# moire_v1_2.net
KiCad netlist of a schematic drawn in EAGLE
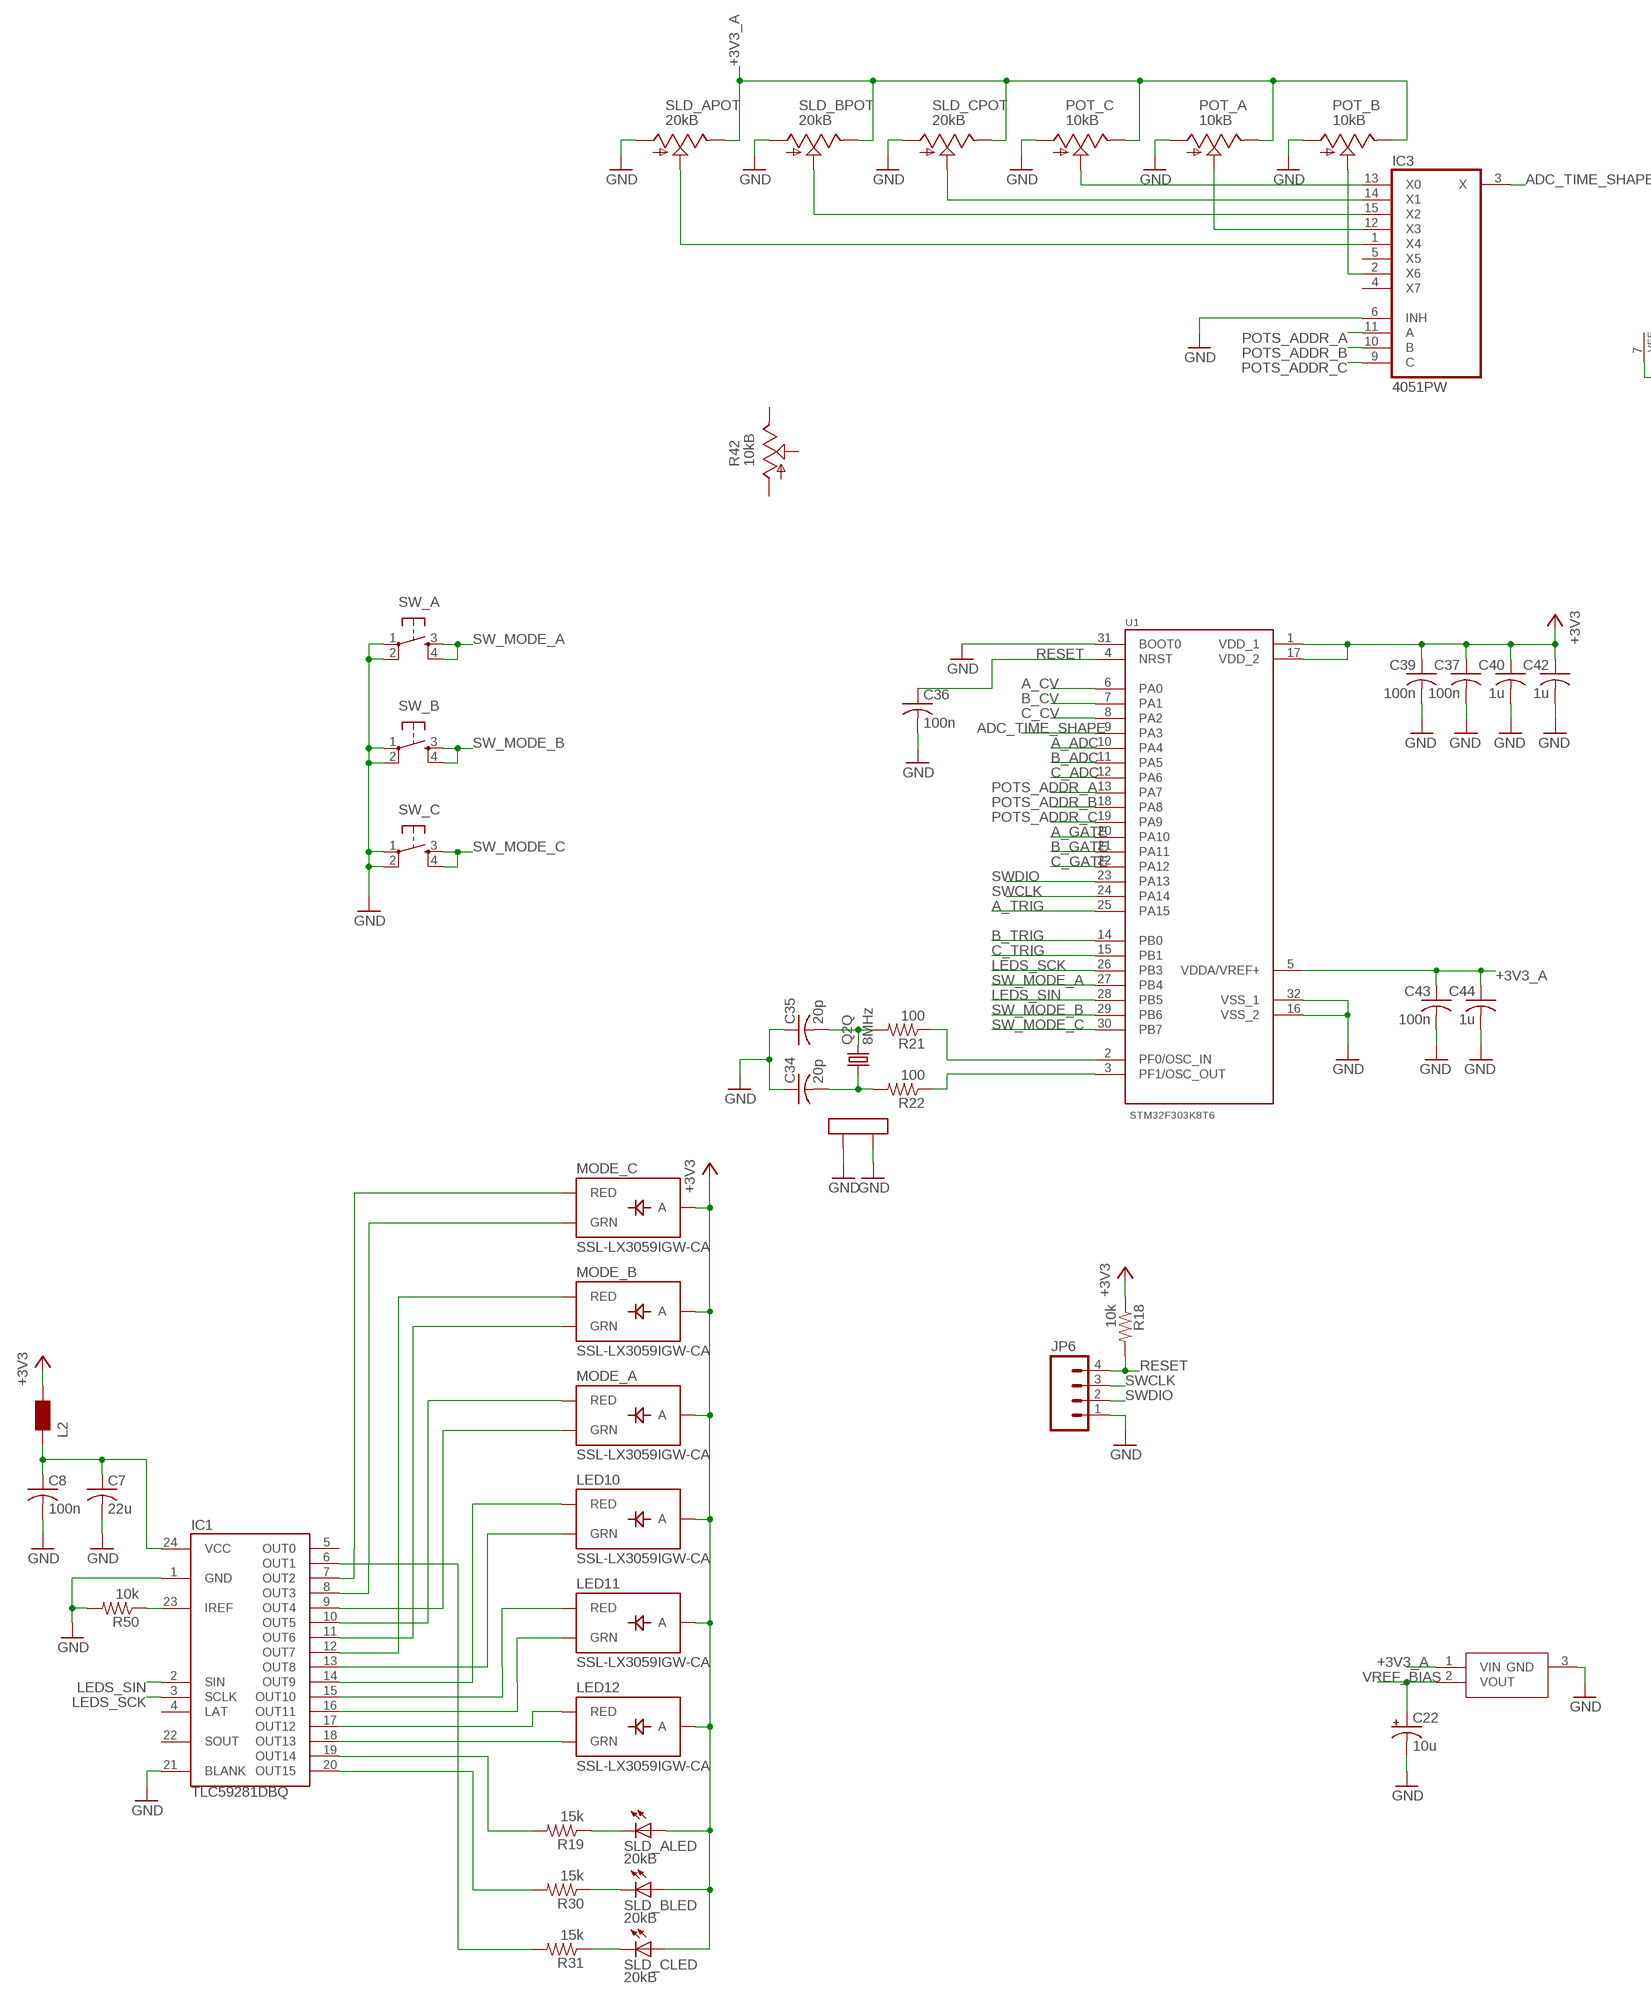
[diagram p0: schematic, sheet 1, part 1 of 2]
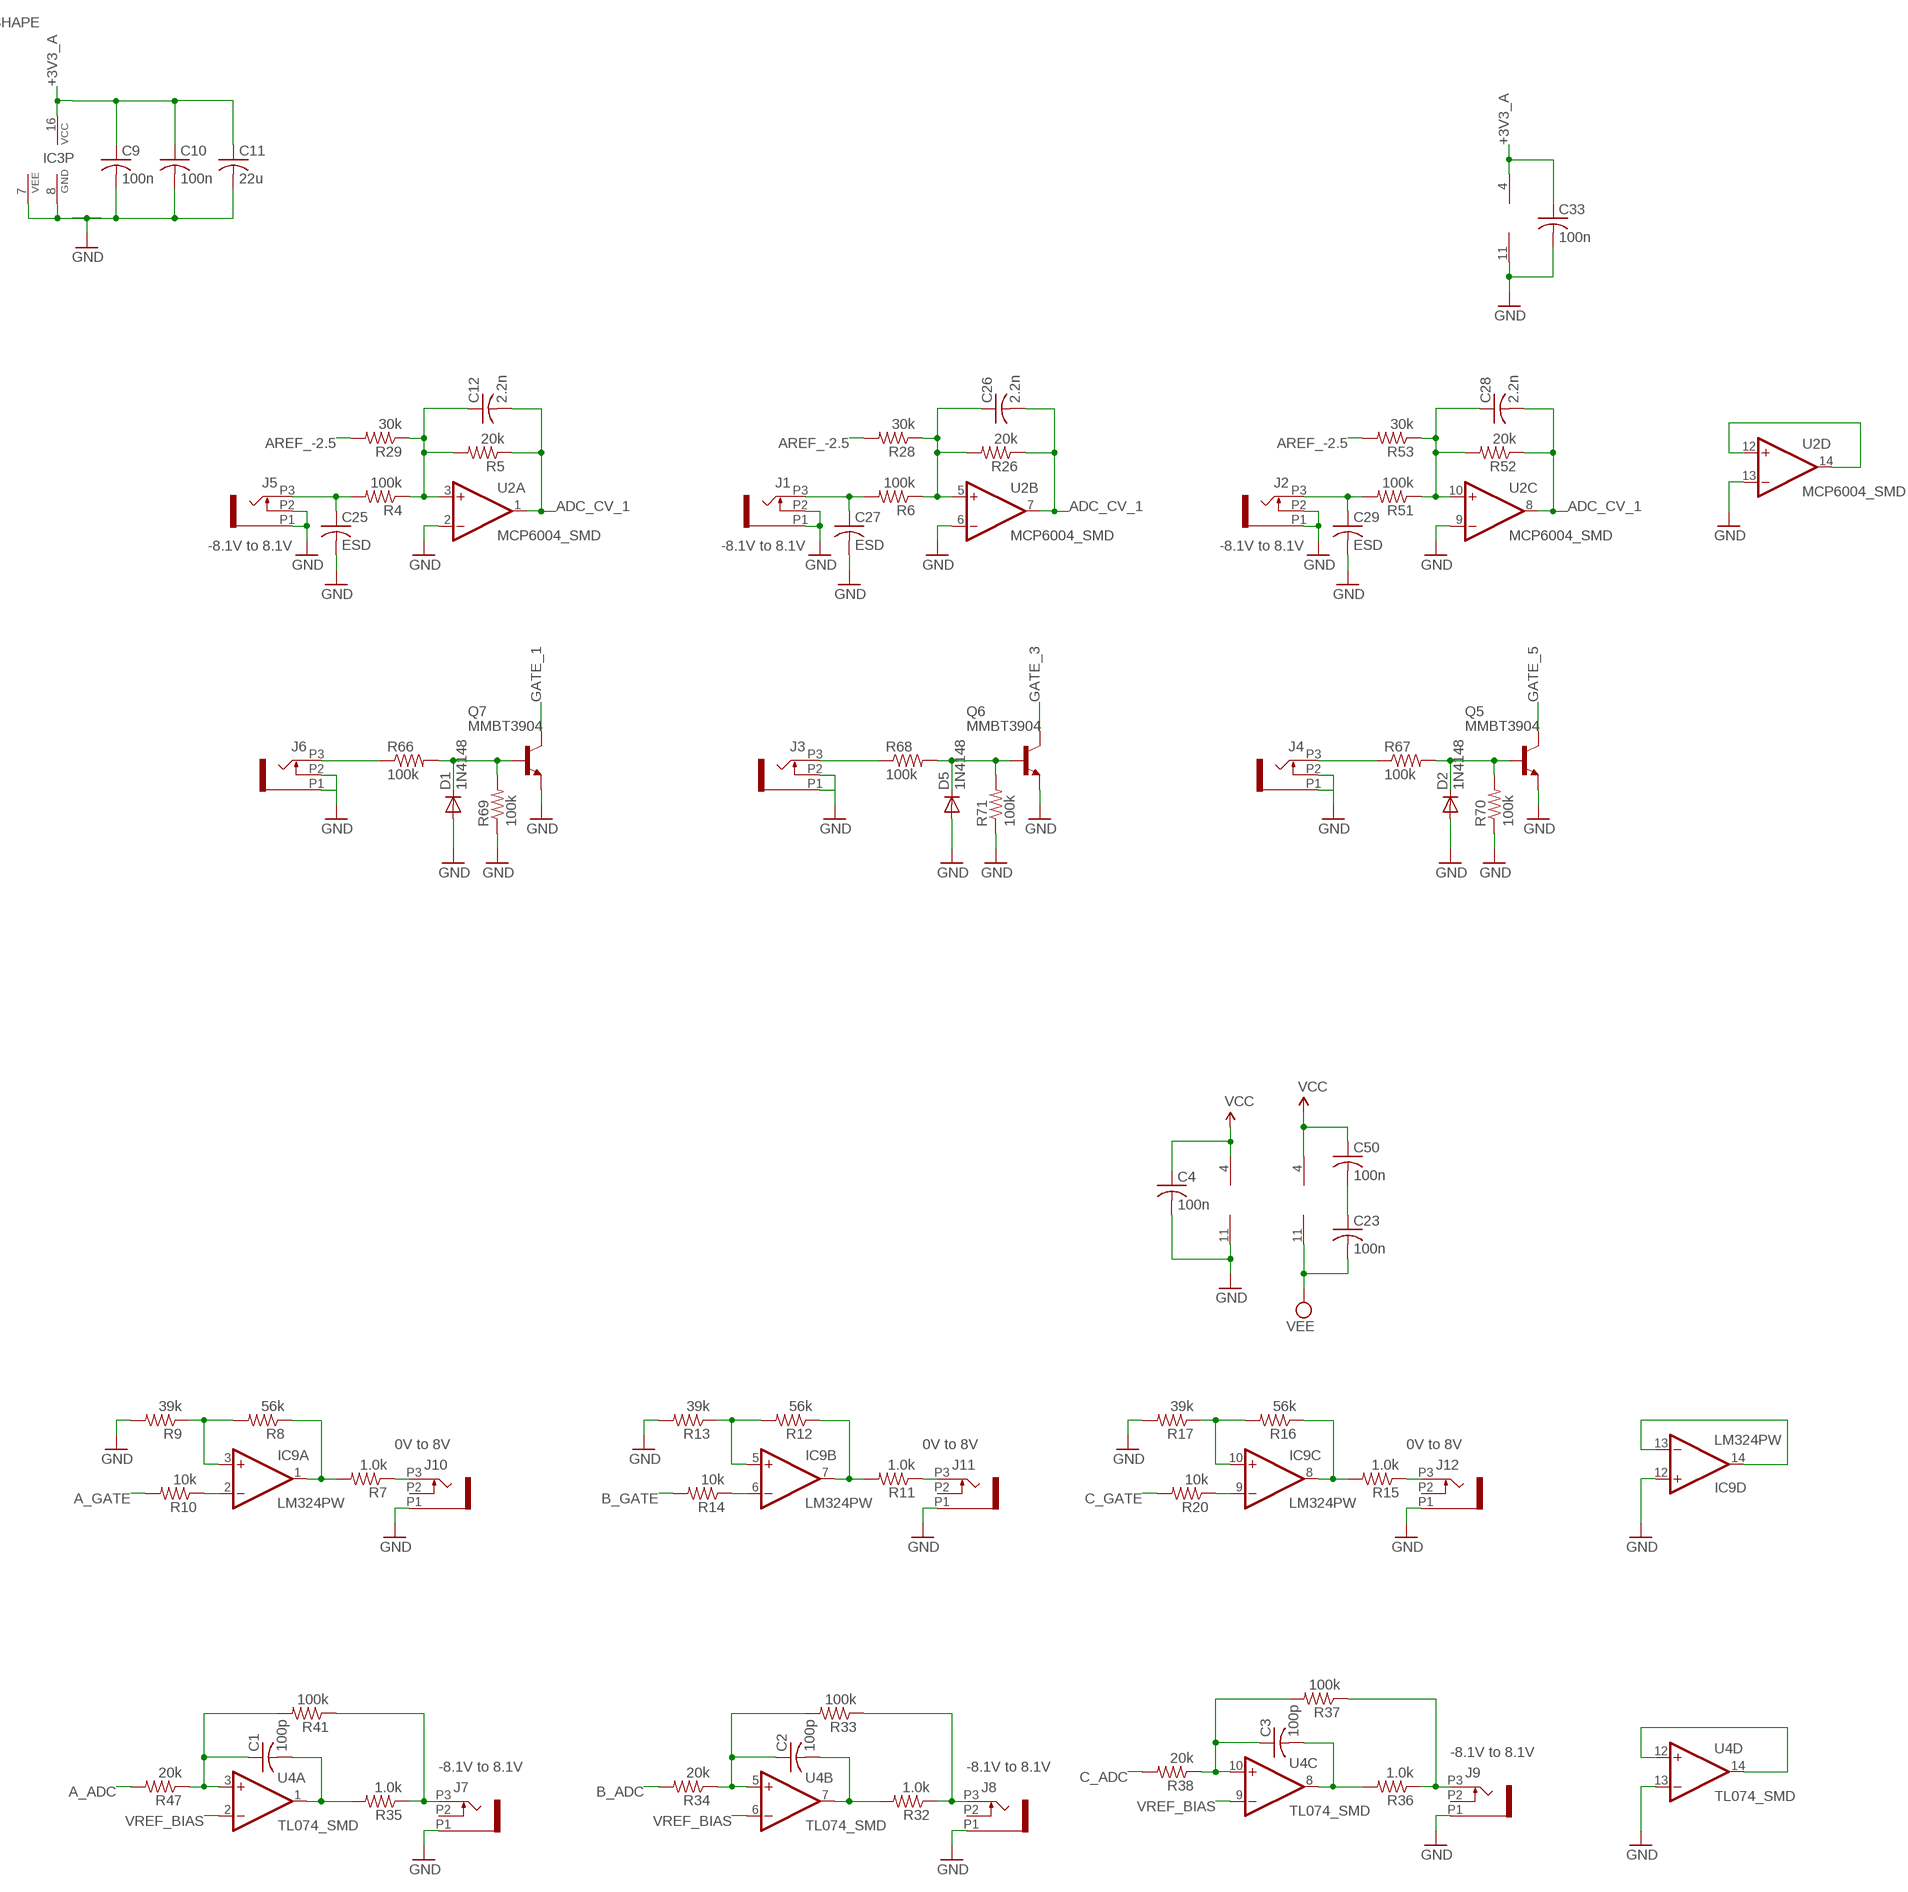
[diagram p1: schematic, sheet 1, part 2 of 2]
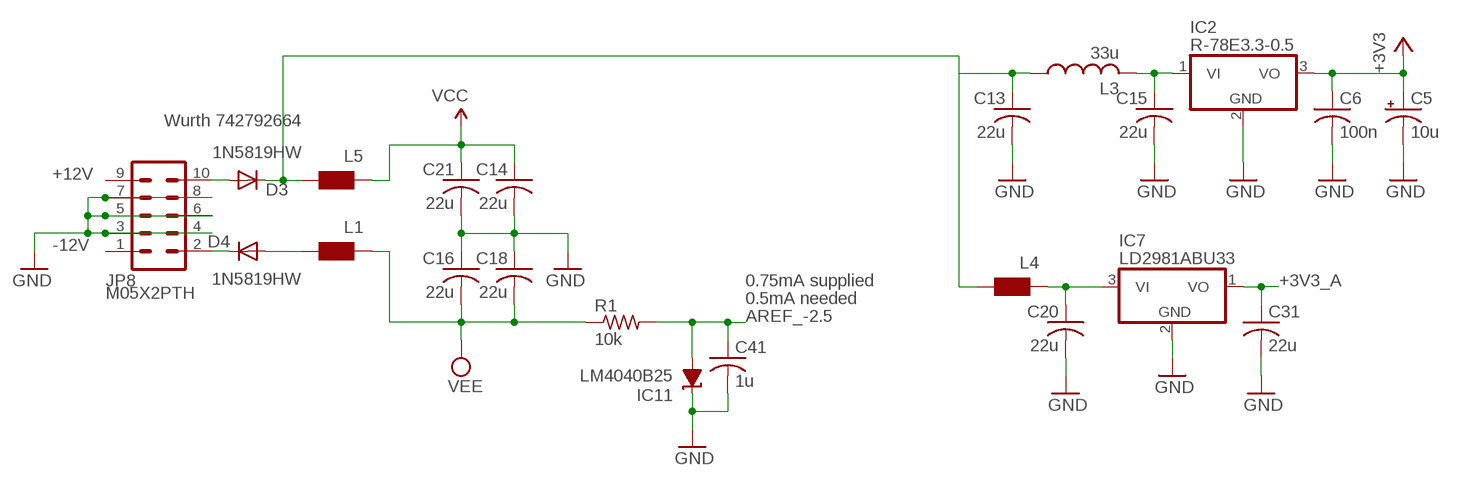
[diagram p2: schematic, sheet 2]

(export (version "E")
  (design (tool "Eeschema 10.0.6"))
  (components
    (comp (ref "C1")
      (value "100p")
      (footprint "eagle-import:C0603")
      (libsource (lib "eagle-import") (part "C-USC0603"))
    )
    (comp (ref "C2")
      (value "100p")
      (footprint "eagle-import:C0603")
      (libsource (lib "eagle-import") (part "C-USC0603"))
    )
    (comp (ref "C3")
      (value "100p")
      (footprint "eagle-import:C0603")
      (libsource (lib "eagle-import") (part "C-USC0603"))
    )
    (comp (ref "C4")
      (value "100n")
      (footprint "eagle-import:C0402")
      (libsource (lib "eagle-import") (part "C-USC0402"))
    )
    (comp (ref "C7")
      (value "22u")
      (footprint "eagle-import:C1206")
      (libsource (lib "eagle-import") (part "C-USC1206"))
    )
    (comp (ref "C8")
      (value "100n")
      (footprint "eagle-import:C0603")
      (libsource (lib "eagle-import") (part "C-USC0603"))
    )
    (comp (ref "C9")
      (value "100n")
      (footprint "eagle-import:C0603")
      (libsource (lib "eagle-import") (part "C-USC0603"))
    )
    (comp (ref "C10")
      (value "100n")
      (footprint "eagle-import:C0603")
      (libsource (lib "eagle-import") (part "C-USC0603"))
    )
    (comp (ref "C11")
      (value "22u")
      (footprint "eagle-import:C1206")
      (libsource (lib "eagle-import") (part "C-USC1206"))
    )
    (comp (ref "C12")
      (value "2.2n")
      (footprint "eagle-import:C0402")
      (libsource (lib "eagle-import") (part "C-USC0402"))
    )
    (comp (ref "C22")
      (value "10u")
      (footprint "eagle-import:PANASONIC_A")
      (libsource (lib "eagle-import") (part "CPOL-USA"))
    )
    (comp (ref "C23")
      (value "100n")
      (footprint "eagle-import:C0603")
      (libsource (lib "eagle-import") (part "C-USC0603"))
    )
    (comp (ref "C25")
      (value "ESD")
      (footprint "eagle-import:C0603")
      (libsource (lib "eagle-import") (part "C-USC0603"))
    )
    (comp (ref "C26")
      (value "2.2n")
      (footprint "eagle-import:C0402")
      (libsource (lib "eagle-import") (part "C-USC0402"))
    )
    (comp (ref "C27")
      (value "ESD")
      (footprint "eagle-import:C0603")
      (libsource (lib "eagle-import") (part "C-USC0603"))
    )
    (comp (ref "C28")
      (value "2.2n")
      (footprint "eagle-import:C0402")
      (libsource (lib "eagle-import") (part "C-USC0402"))
    )
    (comp (ref "C29")
      (value "ESD")
      (footprint "eagle-import:C0603")
      (libsource (lib "eagle-import") (part "C-USC0603"))
    )
    (comp (ref "C33")
      (value "100n")
      (footprint "eagle-import:C0603")
      (libsource (lib "eagle-import") (part "C-USC0603"))
    )
    (comp (ref "C34")
      (value "20p")
      (footprint "eagle-import:C0603")
      (libsource (lib "eagle-import") (part "C-USC0603"))
    )
    (comp (ref "C35")
      (value "20p")
      (footprint "eagle-import:C0603")
      (libsource (lib "eagle-import") (part "C-USC0603"))
    )
    (comp (ref "C36")
      (value "100n")
      (footprint "eagle-import:C0603")
      (libsource (lib "eagle-import") (part "C-USC0603"))
    )
    (comp (ref "C37")
      (value "100n")
      (footprint "eagle-import:C0603")
      (libsource (lib "eagle-import") (part "C-USC0603"))
    )
    (comp (ref "C39")
      (value "100n")
      (footprint "eagle-import:C0603")
      (libsource (lib "eagle-import") (part "C-USC0603"))
    )
    (comp (ref "C40")
      (value "1u")
      (footprint "eagle-import:C0603")
      (libsource (lib "eagle-import") (part "C-USC0603"))
    )
    (comp (ref "C42")
      (value "1u")
      (footprint "eagle-import:C0603")
      (libsource (lib "eagle-import") (part "C-USC0603"))
    )
    (comp (ref "C43")
      (value "100n")
      (footprint "eagle-import:C0603")
      (libsource (lib "eagle-import") (part "C-USC0603"))
    )
    (comp (ref "C44")
      (value "1u")
      (footprint "eagle-import:C0603")
      (libsource (lib "eagle-import") (part "C-USC0603"))
    )
    (comp (ref "C50")
      (value "100n")
      (footprint "eagle-import:C0603")
      (libsource (lib "eagle-import") (part "C-USC0603"))
    )
    (comp (ref "D1")
      (value "1N4148")
      (footprint "eagle-import:SOD523")
      (libsource (lib "eagle-import") (part "DIODE-SOD523"))
    )
    (comp (ref "D2")
      (value "1N4148")
      (footprint "eagle-import:SOD523")
      (libsource (lib "eagle-import") (part "DIODE-SOD523"))
    )
    (comp (ref "D5")
      (value "1N4148")
      (footprint "eagle-import:SOD523")
      (libsource (lib "eagle-import") (part "DIODE-SOD523"))
    )
    (comp (ref "IC1")
      (value "TLC59281DBQ")
      (footprint "eagle-import:TSSOP24_0635")
      (libsource (lib "eagle-import") (part "TLC59281DBQ"))
    )
    (comp (ref "IC3")
      (value "4051PW")
      (footprint "eagle-import:TSSOP16_065")
      (libsource (lib "eagle-import") (part "4051PW"))
    )
    (comp (ref "IC4")
      (value "LM324PW")
      (footprint "eagle-import:TSSOP14_065")
      (libsource (lib "eagle-import") (part "TL074PW"))
    )
    (comp (ref "IC9")
      (value "LM324PW")
      (footprint "eagle-import:TSSOP14_065")
      (libsource (lib "eagle-import") (part "TL074PW"))
    )
    (comp (ref "J1")
      (value "PJ301_THONKICONN6")
      (footprint "eagle-import:WQP_PJ_301M6")
      (libsource (lib "eagle-import") (part "PJ301_THONKICONN6"))
    )
    (comp (ref "J2")
      (value "PJ301_THONKICONN6")
      (footprint "eagle-import:WQP_PJ_301M6")
      (libsource (lib "eagle-import") (part "PJ301_THONKICONN6"))
    )
    (comp (ref "J3")
      (value "PJ301_THONKICONN6")
      (footprint "eagle-import:WQP_PJ_301M6")
      (libsource (lib "eagle-import") (part "PJ301_THONKICONN6"))
    )
    (comp (ref "J4")
      (value "PJ301_THONKICONN6")
      (footprint "eagle-import:WQP_PJ_301M6")
      (libsource (lib "eagle-import") (part "PJ301_THONKICONN6"))
    )
    (comp (ref "J5")
      (value "PJ301_THONKICONN6")
      (footprint "eagle-import:WQP_PJ_301M6")
      (libsource (lib "eagle-import") (part "PJ301_THONKICONN6"))
    )
    (comp (ref "J6")
      (value "PJ301_THONKICONN6")
      (footprint "eagle-import:WQP_PJ_301M6")
      (libsource (lib "eagle-import") (part "PJ301_THONKICONN6"))
    )
    (comp (ref "J7")
      (value "PJ301_THONKICONN6")
      (footprint "eagle-import:WQP_PJ_301M6")
      (libsource (lib "eagle-import") (part "PJ301_THONKICONN6"))
    )
    (comp (ref "J8")
      (value "PJ301_THONKICONN6")
      (footprint "eagle-import:WQP_PJ_301M6")
      (libsource (lib "eagle-import") (part "PJ301_THONKICONN6"))
    )
    (comp (ref "J9")
      (value "PJ301_THONKICONN6")
      (footprint "eagle-import:WQP_PJ_301M6")
      (libsource (lib "eagle-import") (part "PJ301_THONKICONN6"))
    )
    (comp (ref "J10")
      (value "PJ301_THONKICONN6")
      (footprint "eagle-import:WQP_PJ_301M6")
      (libsource (lib "eagle-import") (part "PJ301_THONKICONN6"))
    )
    (comp (ref "J11")
      (value "PJ301_THONKICONN6")
      (footprint "eagle-import:WQP_PJ_301M6")
      (libsource (lib "eagle-import") (part "PJ301_THONKICONN6"))
    )
    (comp (ref "J12")
      (value "PJ301_THONKICONN6")
      (footprint "eagle-import:WQP_PJ_301M6")
      (libsource (lib "eagle-import") (part "PJ301_THONKICONN6"))
    )
    (comp (ref "JP6")
      (value "M04PTH")
      (footprint "eagle-import:1X04")
      (libsource (lib "eagle-import") (part "M04PTH"))
    )
    (comp (ref "L2")
      (value "WE-CBF_0603")
      (footprint "eagle-import:0603")
      (libsource (lib "eagle-import") (part "WE-CBF_0603"))
    )
    (comp (ref "LED10")
      (value "SSL-LX3059IGW-CA")
      (footprint "eagle-import:LED-BICOLOR-THROUGHHOLE-LUMEX")
      (libsource (lib "eagle-import") (part "LED-BICOLOR-THROUGHHOLE-CA"))
    )
    (comp (ref "LED11")
      (value "SSL-LX3059IGW-CA")
      (footprint "eagle-import:LED-BICOLOR-THROUGHHOLE-LUMEX")
      (libsource (lib "eagle-import") (part "LED-BICOLOR-THROUGHHOLE-CA"))
    )
    (comp (ref "LED12")
      (value "SSL-LX3059IGW-CA")
      (footprint "eagle-import:LED-BICOLOR-THROUGHHOLE-LUMEX")
      (libsource (lib "eagle-import") (part "LED-BICOLOR-THROUGHHOLE-CA"))
    )
    (comp (ref "MODE_A")
      (value "SSL-LX3059IGW-CA")
      (footprint "eagle-import:LED-BICOLOR-THROUGHHOLE-LUMEX")
      (libsource (lib "eagle-import") (part "LED-BICOLOR-THROUGHHOLE-CA"))
    )
    (comp (ref "MODE_B")
      (value "SSL-LX3059IGW-CA")
      (footprint "eagle-import:LED-BICOLOR-THROUGHHOLE-LUMEX")
      (libsource (lib "eagle-import") (part "LED-BICOLOR-THROUGHHOLE-CA"))
    )
    (comp (ref "MODE_C")
      (value "SSL-LX3059IGW-CA")
      (footprint "eagle-import:LED-BICOLOR-THROUGHHOLE-LUMEX")
      (libsource (lib "eagle-import") (part "LED-BICOLOR-THROUGHHOLE-CA"))
    )
    (comp (ref "POT_A")
      (value "10kB")
      (footprint "eagle-import:ALPS_POT_VERTICAL")
      (libsource (lib "eagle-import") (part "POT_USVERTICAL"))
    )
    (comp (ref "POT_B")
      (value "10kB")
      (footprint "eagle-import:ALPS_POT_VERTICAL")
      (libsource (lib "eagle-import") (part "POT_USVERTICAL"))
    )
    (comp (ref "POT_C")
      (value "10kB")
      (footprint "eagle-import:ALPS_POT_VERTICAL")
      (libsource (lib "eagle-import") (part "POT_USVERTICAL"))
    )
    (comp (ref "Q2")
      (value "8MHz")
      (footprint "eagle-import:CTS406")
      (libsource (lib "eagle-import") (part "CRYSTAL"))
    )
    (comp (ref "Q5")
      (value "MMBT3904")
      (footprint "eagle-import:SOT23-BEC")
      (libsource (lib "eagle-import") (part "-NPN-SOT23-BECMMBT3904LT1"))
    )
    (comp (ref "Q6")
      (value "MMBT3904")
      (footprint "eagle-import:SOT23-BEC")
      (libsource (lib "eagle-import") (part "-NPN-SOT23-BECMMBT3904LT1"))
    )
    (comp (ref "Q7")
      (value "MMBT3904")
      (footprint "eagle-import:SOT23-BEC")
      (libsource (lib "eagle-import") (part "-NPN-SOT23-BECMMBT3904LT1"))
    )
    (comp (ref "R4")
      (value "100k")
      (footprint "eagle-import:R0603")
      (libsource (lib "eagle-import") (part "R-US_R0603"))
    )
    (comp (ref "R5")
      (value "20k")
      (footprint "eagle-import:R0603")
      (libsource (lib "eagle-import") (part "R-US_R0603"))
    )
    (comp (ref "R6")
      (value "100k")
      (footprint "eagle-import:R0603")
      (libsource (lib "eagle-import") (part "R-US_R0603"))
    )
    (comp (ref "R7")
      (value "1.0k")
      (footprint "eagle-import:R0603")
      (libsource (lib "eagle-import") (part "R-US_R0603"))
    )
    (comp (ref "R8")
      (value "56k")
      (footprint "eagle-import:R0603")
      (libsource (lib "eagle-import") (part "R-US_R0603"))
    )
    (comp (ref "R9")
      (value "39k")
      (footprint "eagle-import:R0603")
      (libsource (lib "eagle-import") (part "R-US_R0603"))
    )
    (comp (ref "R10")
      (value "10k")
      (footprint "eagle-import:R0603")
      (libsource (lib "eagle-import") (part "R-US_R0603"))
    )
    (comp (ref "R11")
      (value "1.0k")
      (footprint "eagle-import:R0603")
      (libsource (lib "eagle-import") (part "R-US_R0603"))
    )
    (comp (ref "R12")
      (value "56k")
      (footprint "eagle-import:R0603")
      (libsource (lib "eagle-import") (part "R-US_R0603"))
    )
    (comp (ref "R13")
      (value "39k")
      (footprint "eagle-import:R0603")
      (libsource (lib "eagle-import") (part "R-US_R0603"))
    )
    (comp (ref "R14")
      (value "10k")
      (footprint "eagle-import:R0603")
      (libsource (lib "eagle-import") (part "R-US_R0603"))
    )
    (comp (ref "R15")
      (value "1.0k")
      (footprint "eagle-import:R0603")
      (libsource (lib "eagle-import") (part "R-US_R0603"))
    )
    (comp (ref "R16")
      (value "56k")
      (footprint "eagle-import:R0603")
      (libsource (lib "eagle-import") (part "R-US_R0603"))
    )
    (comp (ref "R17")
      (value "39k")
      (footprint "eagle-import:R0603")
      (libsource (lib "eagle-import") (part "R-US_R0603"))
    )
    (comp (ref "R18")
      (value "10k")
      (footprint "eagle-import:R0603")
      (libsource (lib "eagle-import") (part "R-US_R0603"))
    )
    (comp (ref "R19")
      (value "15k")
      (footprint "eagle-import:R0603")
      (libsource (lib "eagle-import") (part "R-US_R0603"))
    )
    (comp (ref "R20")
      (value "10k")
      (footprint "eagle-import:R0603")
      (libsource (lib "eagle-import") (part "R-US_R0603"))
    )
    (comp (ref "R21")
      (value "100")
      (footprint "eagle-import:R0603")
      (libsource (lib "eagle-import") (part "R-US_R0603"))
    )
    (comp (ref "R22")
      (value "100")
      (footprint "eagle-import:R0603")
      (libsource (lib "eagle-import") (part "R-US_R0603"))
    )
    (comp (ref "R26")
      (value "20k")
      (footprint "eagle-import:R0603")
      (libsource (lib "eagle-import") (part "R-US_R0603"))
    )
    (comp (ref "R28")
      (value "30k")
      (footprint "eagle-import:R0603")
      (libsource (lib "eagle-import") (part "R-US_R0603"))
    )
    (comp (ref "R29")
      (value "30k")
      (footprint "eagle-import:R0603")
      (libsource (lib "eagle-import") (part "R-US_R0603"))
    )
    (comp (ref "R30")
      (value "15k")
      (footprint "eagle-import:R0603")
      (libsource (lib "eagle-import") (part "R-US_R0603"))
    )
    (comp (ref "R31")
      (value "15k")
      (footprint "eagle-import:R0603")
      (libsource (lib "eagle-import") (part "R-US_R0603"))
    )
    (comp (ref "R32")
      (value "1.0k")
      (footprint "eagle-import:R0603")
      (libsource (lib "eagle-import") (part "R-US_R0603"))
    )
    (comp (ref "R33")
      (value "100k")
      (footprint "eagle-import:R0603")
      (libsource (lib "eagle-import") (part "R-US_R0603"))
    )
    (comp (ref "R34")
      (value "20k")
      (footprint "eagle-import:R0603")
      (libsource (lib "eagle-import") (part "R-US_R0603"))
    )
    (comp (ref "R35")
      (value "1.0k")
      (footprint "eagle-import:R0603")
      (libsource (lib "eagle-import") (part "R-US_R0603"))
    )
    (comp (ref "R36")
      (value "1.0k")
      (footprint "eagle-import:R0603")
      (libsource (lib "eagle-import") (part "R-US_R0603"))
    )
    (comp (ref "R37")
      (value "100k")
      (footprint "eagle-import:R0603")
      (libsource (lib "eagle-import") (part "R-US_R0603"))
    )
    (comp (ref "R38")
      (value "20k")
      (footprint "eagle-import:R0603")
      (libsource (lib "eagle-import") (part "R-US_R0603"))
    )
    (comp (ref "R41")
      (value "100k")
      (footprint "eagle-import:R0603")
      (libsource (lib "eagle-import") (part "R-US_R0603"))
    )
    (comp (ref "R42")
      (value "10kB")
      (footprint "eagle-import:ALPS_POT_VERTICAL")
      (libsource (lib "eagle-import") (part "POT_USVERTICAL"))
    )
    (comp (ref "R47")
      (value "20k")
      (footprint "eagle-import:R0603")
      (libsource (lib "eagle-import") (part "R-US_R0603"))
    )
    (comp (ref "R50")
      (value "10k")
      (footprint "eagle-import:R0603")
      (libsource (lib "eagle-import") (part "R-US_R0603"))
    )
    (comp (ref "R51")
      (value "100k")
      (footprint "eagle-import:R0603")
      (libsource (lib "eagle-import") (part "R-US_R0603"))
    )
    (comp (ref "R52")
      (value "20k")
      (footprint "eagle-import:R0603")
      (libsource (lib "eagle-import") (part "R-US_R0603"))
    )
    (comp (ref "R53")
      (value "30k")
      (footprint "eagle-import:R0603")
      (libsource (lib "eagle-import") (part "R-US_R0603"))
    )
    (comp (ref "R66")
      (value "100k")
      (footprint "eagle-import:R0603")
      (libsource (lib "eagle-import") (part "R-US_R0603"))
    )
    (comp (ref "R67")
      (value "100k")
      (footprint "eagle-import:R0603")
      (libsource (lib "eagle-import") (part "R-US_R0603"))
    )
    (comp (ref "R68")
      (value "100k")
      (footprint "eagle-import:R0603")
      (libsource (lib "eagle-import") (part "R-US_R0603"))
    )
    (comp (ref "R69")
      (value "100k")
      (footprint "eagle-import:R0603")
      (libsource (lib "eagle-import") (part "R-US_R0603"))
    )
    (comp (ref "R70")
      (value "100k")
      (footprint "eagle-import:R0603")
      (libsource (lib "eagle-import") (part "R-US_R0603"))
    )
    (comp (ref "R71")
      (value "100k")
      (footprint "eagle-import:R0603")
      (libsource (lib "eagle-import") (part "R-US_R0603"))
    )
    (comp (ref "SLD_A")
      (value "20kB")
      (footprint "eagle-import:BOURNS_SLIDER")
      (libsource (lib "eagle-import") (part "BOURNS_SLIDER"))
    )
    (comp (ref "SLD_B")
      (value "20kB")
      (footprint "eagle-import:BOURNS_SLIDER")
      (libsource (lib "eagle-import") (part "BOURNS_SLIDER"))
    )
    (comp (ref "SLD_C")
      (value "20kB")
      (footprint "eagle-import:BOURNS_SLIDER")
      (libsource (lib "eagle-import") (part "BOURNS_SLIDER"))
    )
    (comp (ref "SW_A")
      (value "TAC_SWITCHPTH")
      (footprint "eagle-import:TACTILE-PTH")
      (libsource (lib "eagle-import") (part "TAC_SWITCHPTH"))
    )
    (comp (ref "SW_B")
      (value "TAC_SWITCHPTH")
      (footprint "eagle-import:TACTILE-PTH")
      (libsource (lib "eagle-import") (part "TAC_SWITCHPTH"))
    )
    (comp (ref "SW_C")
      (value "TAC_SWITCHPTH")
      (footprint "eagle-import:TACTILE-PTH")
      (libsource (lib "eagle-import") (part "TAC_SWITCHPTH"))
    )
    (comp (ref "U$1")
      (value "ISL21010")
      (footprint "eagle-import:SOT-23-3")
      (libsource (lib "eagle-import") (part "ISL21010"))
    )
    (comp (ref "U1")
      (value "STM32F303K8T6")
      (footprint "eagle-import:QFP80P900X900X160-32N")
      (fields (field (name "MF") "STMicroelectronics"))
      (libsource (lib "eagle-import") (part "STM32F303K8T6"))
    )
    (comp (ref "U2")
      (value "MCP6004_SMD")
      (footprint "eagle-import:SO14")
      (libsource (lib "eagle-import") (part "MCP6004_SMD"))
    )
    (comp (ref "U4")
      (value "TL074_SMD")
      (footprint "eagle-import:SO14")
      (libsource (lib "eagle-import") (part "TL074_SMD"))
    )
    (comp (ref "C5")
      (value "10u")
      (footprint "eagle-import:PANASONIC_A")
      (libsource (lib "eagle-import") (part "CPOL-USA"))
    )
    (comp (ref "C6")
      (value "100n")
      (footprint "eagle-import:C0402")
      (libsource (lib "eagle-import") (part "C-USC0402"))
    )
    (comp (ref "C13")
      (value "22u")
      (footprint "eagle-import:C1206")
      (libsource (lib "eagle-import") (part "C-USC1206"))
    )
    (comp (ref "C14")
      (value "22u")
      (footprint "eagle-import:C1206")
      (libsource (lib "eagle-import") (part "C-USC1206"))
    )
    (comp (ref "C15")
      (value "22u")
      (footprint "eagle-import:C1206")
      (libsource (lib "eagle-import") (part "C-USC1206"))
    )
    (comp (ref "C16")
      (value "22u")
      (footprint "eagle-import:C1206")
      (libsource (lib "eagle-import") (part "C-USC1206"))
    )
    (comp (ref "C18")
      (value "22u")
      (footprint "eagle-import:C1206")
      (libsource (lib "eagle-import") (part "C-USC1206"))
    )
    (comp (ref "C20")
      (value "22u")
      (footprint "eagle-import:C1206")
      (libsource (lib "eagle-import") (part "C-USC1206"))
    )
    (comp (ref "C21")
      (value "22u")
      (footprint "eagle-import:C1206")
      (libsource (lib "eagle-import") (part "C-USC1206"))
    )
    (comp (ref "C31")
      (value "22u")
      (footprint "eagle-import:C1206")
      (libsource (lib "eagle-import") (part "C-USC1206"))
    )
    (comp (ref "C41")
      (value "1u")
      (footprint "eagle-import:C0402")
      (libsource (lib "eagle-import") (part "C-USC0402"))
    )
    (comp (ref "D3")
      (value "1N5819HW")
      (footprint "eagle-import:SOD123")
      (libsource (lib "eagle-import") (part "DIODE-SOD123"))
    )
    (comp (ref "D4")
      (value "1N5819HW")
      (footprint "eagle-import:SOD123")
      (libsource (lib "eagle-import") (part "DIODE-SOD123"))
    )
    (comp (ref "IC2")
      (value "R-78E3.3-0.5")
      (footprint "eagle-import:WE78")
      (libsource (lib "eagle-import") (part "WE173950378"))
    )
    (comp (ref "IC7")
      (value "LD2981ABU33")
      (footprint "eagle-import:SOT89")
      (libsource (lib "eagle-import") (part "LD2981ABU"))
    )
    (comp (ref "IC11")
      (value "LM4040B25")
      (footprint "eagle-import:DBZ_R-PDSO-G3")
      (libsource (lib "eagle-import") (part "LM4041DBZB12"))
    )
    (comp (ref "JP8")
      (value "M05X2PTH")
      (footprint "eagle-import:2X5-PTH")
      (libsource (lib "eagle-import") (part "M05X2PTH"))
    )
    (comp (ref "L1")
      (value "WE-CBF_0603")
      (footprint "eagle-import:0603")
      (libsource (lib "eagle-import") (part "WE-CBF_0603"))
    )
    (comp (ref "L3")
      (value "33u")
      (footprint "eagle-import:L2012C")
      (libsource (lib "eagle-import") (part "L-USL2012C"))
    )
    (comp (ref "L4")
      (value "WE-CBF_0603")
      (footprint "eagle-import:0603")
      (libsource (lib "eagle-import") (part "WE-CBF_0603"))
    )
    (comp (ref "L5")
      (value "WE-CBF_0603")
      (footprint "eagle-import:0603")
      (libsource (lib "eagle-import") (part "WE-CBF_0603"))
    )
    (comp (ref "R1")
      (value "10k")
      (footprint "eagle-import:R0603")
      (libsource (lib "eagle-import") (part "R-US_R0603"))
    )
  )
  (nets
    (net (code "1") (name "+3V3") (class "Default")
      (node (ref "C37") (pin "1") (pinfunction "1_1") (pintype "passive"))
      (node (ref "C39") (pin "1") (pinfunction "1_1") (pintype "passive"))
      (node (ref "C40") (pin "1") (pinfunction "1_1") (pintype "passive"))
      (node (ref "C42") (pin "1") (pinfunction "1_1") (pintype "passive"))
      (node (ref "C5") (pin "+") (pinfunction "+_+") (pintype "passive"))
      (node (ref "C6") (pin "1") (pinfunction "1_1") (pintype "passive"))
      (node (ref "IC2") (pin "3") (pinfunction "VO_3") (pintype "passive"))
      (node (ref "L2") (pin "2") (pinfunction "2_2") (pintype "passive"))
      (node (ref "LED10") (pin "A") (pinfunction "A_A") (pintype "bidirectional"))
      (node (ref "LED11") (pin "A") (pinfunction "A_A") (pintype "bidirectional"))
      (node (ref "LED12") (pin "A") (pinfunction "A_A") (pintype "bidirectional"))
      (node (ref "MODE_A") (pin "A") (pinfunction "A_A") (pintype "bidirectional"))
      (node (ref "MODE_B") (pin "A") (pinfunction "A_A") (pintype "bidirectional"))
      (node (ref "MODE_C") (pin "A") (pinfunction "A_A") (pintype "bidirectional"))
      (node (ref "R18") (pin "1") (pinfunction "1_1") (pintype "passive"))
      (node (ref "SLD_A") (pin "B") (pinfunction "A_B") (pintype "passive"))
      (node (ref "SLD_B") (pin "B") (pinfunction "A_B") (pintype "passive"))
      (node (ref "SLD_C") (pin "B") (pinfunction "A_B") (pintype "passive"))
      (node (ref "U1") (pin "1") (pinfunction "VDD_1_1") (pintype "power_in"))
      (node (ref "U1") (pin "17") (pinfunction "VDD_2_17") (pintype "power_in"))
    )
    (net (code "2") (name "+3V3_A") (class "Default")
      (node (ref "C10") (pin "1") (pinfunction "1_1") (pintype "passive"))
      (node (ref "C11") (pin "1") (pinfunction "1_1") (pintype "passive"))
      (node (ref "C31") (pin "1") (pinfunction "1_1") (pintype "passive"))
      (node (ref "C33") (pin "1") (pinfunction "1_1") (pintype "passive"))
      (node (ref "C43") (pin "1") (pinfunction "1_1") (pintype "passive"))
      (node (ref "C44") (pin "1") (pinfunction "1_1") (pintype "passive"))
      (node (ref "C9") (pin "1") (pinfunction "1_1") (pintype "passive"))
      (node (ref "IC3") (pin "16") (pinfunction "VCC_16") (pintype "power_in"))
      (node (ref "IC7") (pin "1") (pinfunction "VO_1") (pintype "passive"))
      (node (ref "POT_A") (pin "P$1") (pinfunction "E_P$1") (pintype "passive"))
      (node (ref "POT_B") (pin "P$1") (pinfunction "E_P$1") (pintype "passive"))
      (node (ref "POT_C") (pin "P$1") (pinfunction "E_P$1") (pintype "passive"))
      (node (ref "SLD_A") (pin "3") (pinfunction "E_3") (pintype "passive"))
      (node (ref "SLD_B") (pin "3") (pinfunction "E_3") (pintype "passive"))
      (node (ref "SLD_C") (pin "3") (pinfunction "E_3") (pintype "passive"))
      (node (ref "U$1") (pin "1") (pinfunction "VIN_1") (pintype "input"))
      (node (ref "U1") (pin "5") (pinfunction "VDDA/VREF+_5") (pintype "power_in"))
      (node (ref "U2") (pin "4") (pinfunction "V+_4") (pintype "power_in"))
    )
    (net (code "3") (name "+12V") (class "Default")
      (node (ref "D3") (pin "A") (pinfunction "A_A") (pintype "passive"))
      (node (ref "JP8") (pin "10") (pinfunction "10_10") (pintype "passive"))
    )
    (net (code "4") (name "-12V") (class "Default")
      (node (ref "D4") (pin "C") (pinfunction "C_C") (pintype "passive"))
      (node (ref "JP8") (pin "2") (pinfunction "2_2") (pintype "passive"))
    )
    (net (code "5") (name "ADC_CV_1") (class "Default")
      (node (ref "C12") (pin "2") (pinfunction "2_2") (pintype "passive"))
      (node (ref "C26") (pin "2") (pinfunction "2_2") (pintype "passive"))
      (node (ref "C28") (pin "2") (pinfunction "2_2") (pintype "passive"))
      (node (ref "R26") (pin "1") (pinfunction "1_1") (pintype "passive"))
      (node (ref "R5") (pin "1") (pinfunction "1_1") (pintype "passive"))
      (node (ref "R52") (pin "1") (pinfunction "1_1") (pintype "passive"))
      (node (ref "U2") (pin "1") (pinfunction "OUT_1") (pintype "output"))
      (node (ref "U2") (pin "7") (pinfunction "OUT_7") (pintype "output"))
      (node (ref "U2") (pin "8") (pinfunction "OUT_8") (pintype "output"))
    )
    (net (code "6") (name "ADC_TIME_SHAPE") (class "Default")
      (node (ref "IC3") (pin "3") (pinfunction "X_3") (pintype "bidirectional"))
      (node (ref "U1") (pin "9") (pinfunction "PA3_9") (pintype "bidirectional"))
    )
    (net (code "7") (name "AREF_-2.5") (class "Default")
      (node (ref "C41") (pin "1") (pinfunction "1_1") (pintype "passive"))
      (node (ref "IC11") (pin "2") (pinfunction "A_2") (pintype "passive"))
      (node (ref "R1") (pin "2") (pinfunction "2_2") (pintype "passive"))
      (node (ref "R28") (pin "2") (pinfunction "2_2") (pintype "passive"))
      (node (ref "R29") (pin "2") (pinfunction "2_2") (pintype "passive"))
      (node (ref "R53") (pin "2") (pinfunction "2_2") (pintype "passive"))
    )
    (net (code "8") (name "A_ADC") (class "Default")
      (node (ref "R47") (pin "2") (pinfunction "2_2") (pintype "passive"))
      (node (ref "U1") (pin "10") (pinfunction "PA4_10") (pintype "bidirectional"))
    )
    (net (code "9") (name "A_CV") (class "Default")
      (node (ref "U1") (pin "6") (pinfunction "PA0_6") (pintype "bidirectional"))
    )
    (net (code "10") (name "A_GATE") (class "Default")
      (node (ref "R10") (pin "2") (pinfunction "2_2") (pintype "passive"))
      (node (ref "U1") (pin "20") (pinfunction "PA10_20") (pintype "bidirectional"))
    )
    (net (code "11") (name "A_TRIG") (class "Default")
      (node (ref "U1") (pin "25") (pinfunction "PA15_25") (pintype "bidirectional"))
    )
    (net (code "12") (name "B_ADC") (class "Default")
      (node (ref "R34") (pin "2") (pinfunction "2_2") (pintype "passive"))
      (node (ref "U1") (pin "11") (pinfunction "PA5_11") (pintype "bidirectional"))
    )
    (net (code "13") (name "B_CV") (class "Default")
      (node (ref "U1") (pin "7") (pinfunction "PA1_7") (pintype "bidirectional"))
    )
    (net (code "14") (name "B_GATE") (class "Default")
      (node (ref "R14") (pin "2") (pinfunction "2_2") (pintype "passive"))
      (node (ref "U1") (pin "21") (pinfunction "PA11_21") (pintype "bidirectional"))
    )
    (net (code "15") (name "B_TRIG") (class "Default")
      (node (ref "U1") (pin "14") (pinfunction "PB0_14") (pintype "bidirectional"))
    )
    (net (code "16") (name "C_ADC") (class "Default")
      (node (ref "R38") (pin "2") (pinfunction "2_2") (pintype "passive"))
      (node (ref "U1") (pin "12") (pinfunction "PA6_12") (pintype "bidirectional"))
    )
    (net (code "17") (name "C_CV") (class "Default")
      (node (ref "U1") (pin "8") (pinfunction "PA2_8") (pintype "bidirectional"))
    )
    (net (code "18") (name "C_GATE") (class "Default")
      (node (ref "R20") (pin "2") (pinfunction "2_2") (pintype "passive"))
      (node (ref "U1") (pin "22") (pinfunction "PA12_22") (pintype "bidirectional"))
    )
    (net (code "19") (name "C_TRIG") (class "Default")
      (node (ref "U1") (pin "15") (pinfunction "PB1_15") (pintype "bidirectional"))
    )
    (net (code "20") (name "GATE_1") (class "Default")
      (node (ref "Q7") (pin "C") (pinfunction "C_C") (pintype "passive"))
    )
    (net (code "21") (name "GATE_3") (class "Default")
      (node (ref "Q6") (pin "C") (pinfunction "C_C") (pintype "passive"))
    )
    (net (code "22") (name "GATE_5") (class "Default")
      (node (ref "Q5") (pin "C") (pinfunction "C_C") (pintype "passive"))
    )
    (net (code "23") (name "GND") (class "Default")
      (node (ref "C10") (pin "2") (pinfunction "2_2") (pintype "passive"))
      (node (ref "C11") (pin "2") (pinfunction "2_2") (pintype "passive"))
      (node (ref "C13") (pin "2") (pinfunction "2_2") (pintype "passive"))
      (node (ref "C14") (pin "2") (pinfunction "2_2") (pintype "passive"))
      (node (ref "C15") (pin "2") (pinfunction "2_2") (pintype "passive"))
      (node (ref "C16") (pin "1") (pinfunction "1_1") (pintype "passive"))
      (node (ref "C18") (pin "1") (pinfunction "1_1") (pintype "passive"))
      (node (ref "C20") (pin "2") (pinfunction "2_2") (pintype "passive"))
      (node (ref "C21") (pin "2") (pinfunction "2_2") (pintype "passive"))
      (node (ref "C22") (pin "-") (pinfunction "-_-") (pintype "passive"))
      (node (ref "C25") (pin "2") (pinfunction "2_2") (pintype "passive"))
      (node (ref "C27") (pin "2") (pinfunction "2_2") (pintype "passive"))
      (node (ref "C29") (pin "2") (pinfunction "2_2") (pintype "passive"))
      (node (ref "C31") (pin "2") (pinfunction "2_2") (pintype "passive"))
      (node (ref "C33") (pin "2") (pinfunction "2_2") (pintype "passive"))
      (node (ref "C34") (pin "1") (pinfunction "1_1") (pintype "passive"))
      (node (ref "C35") (pin "1") (pinfunction "1_1") (pintype "passive"))
      (node (ref "C36") (pin "2") (pinfunction "2_2") (pintype "passive"))
      (node (ref "C37") (pin "2") (pinfunction "2_2") (pintype "passive"))
      (node (ref "C39") (pin "2") (pinfunction "2_2") (pintype "passive"))
      (node (ref "C4") (pin "2") (pinfunction "2_2") (pintype "passive"))
      (node (ref "C40") (pin "2") (pinfunction "2_2") (pintype "passive"))
      (node (ref "C41") (pin "2") (pinfunction "2_2") (pintype "passive"))
      (node (ref "C42") (pin "2") (pinfunction "2_2") (pintype "passive"))
      (node (ref "C43") (pin "2") (pinfunction "2_2") (pintype "passive"))
      (node (ref "C44") (pin "2") (pinfunction "2_2") (pintype "passive"))
      (node (ref "C5") (pin "-") (pinfunction "-_-") (pintype "passive"))
      (node (ref "C6") (pin "2") (pinfunction "2_2") (pintype "passive"))
      (node (ref "C7") (pin "2") (pinfunction "2_2") (pintype "passive"))
      (node (ref "C8") (pin "2") (pinfunction "2_2") (pintype "passive"))
      (node (ref "C9") (pin "2") (pinfunction "2_2") (pintype "passive"))
      (node (ref "D1") (pin "A") (pinfunction "A_A") (pintype "passive"))
      (node (ref "D2") (pin "A") (pinfunction "A_A") (pintype "passive"))
      (node (ref "D5") (pin "A") (pinfunction "A_A") (pintype "passive"))
      (node (ref "IC1") (pin "1") (pinfunction "GND_1") (pintype "bidirectional"))
      (node (ref "IC1") (pin "21") (pinfunction "BLANK_21") (pintype "bidirectional"))
      (node (ref "IC11") (pin "1") (pinfunction "C_1") (pintype "passive"))
      (node (ref "IC2") (pin "2") (pinfunction "GND_2") (pintype "passive"))
      (node (ref "IC3") (pin "6") (pinfunction "INH_6") (pintype "input"))
      (node (ref "IC3") (pin "7") (pinfunction "VEE_7") (pintype "power_in"))
      (node (ref "IC3") (pin "8") (pinfunction "GND_8") (pintype "power_in"))
      (node (ref "IC4") (pin "11") (pinfunction "V-_11") (pintype "power_in"))
      (node (ref "IC7") (pin "2") (pinfunction "GND_2") (pintype "passive"))
      (node (ref "IC9") (pin "12") (pinfunction "+IN_12") (pintype "input"))
      (node (ref "J1") (pin "P1") (pinfunction "1_P1") (pintype "passive"))
      (node (ref "J1") (pin "P2") (pinfunction "2_P2") (pintype "passive"))
      (node (ref "J10") (pin "P1") (pinfunction "1_P1") (pintype "passive"))
      (node (ref "J11") (pin "P1") (pinfunction "1_P1") (pintype "passive"))
      (node (ref "J12") (pin "P1") (pinfunction "1_P1") (pintype "passive"))
      (node (ref "J2") (pin "P1") (pinfunction "1_P1") (pintype "passive"))
      (node (ref "J2") (pin "P2") (pinfunction "2_P2") (pintype "passive"))
      (node (ref "J3") (pin "P1") (pinfunction "1_P1") (pintype "passive"))
      (node (ref "J3") (pin "P2") (pinfunction "2_P2") (pintype "passive"))
      (node (ref "J4") (pin "P1") (pinfunction "1_P1") (pintype "passive"))
      (node (ref "J4") (pin "P2") (pinfunction "2_P2") (pintype "passive"))
      (node (ref "J5") (pin "P1") (pinfunction "1_P1") (pintype "passive"))
      (node (ref "J5") (pin "P2") (pinfunction "2_P2") (pintype "passive"))
      (node (ref "J6") (pin "P1") (pinfunction "1_P1") (pintype "passive"))
      (node (ref "J6") (pin "P2") (pinfunction "2_P2") (pintype "passive"))
      (node (ref "J7") (pin "P1") (pinfunction "1_P1") (pintype "passive"))
      (node (ref "J8") (pin "P1") (pinfunction "1_P1") (pintype "passive"))
      (node (ref "J9") (pin "P1") (pinfunction "1_P1") (pintype "passive"))
      (node (ref "JP6") (pin "1") (pinfunction "1_1") (pintype "passive"))
      (node (ref "JP8") (pin "3") (pinfunction "3_3") (pintype "passive"))
      (node (ref "JP8") (pin "4") (pinfunction "4_4") (pintype "passive"))
      (node (ref "JP8") (pin "5") (pinfunction "5_5") (pintype "passive"))
      (node (ref "JP8") (pin "6") (pinfunction "6_6") (pintype "passive"))
      (node (ref "JP8") (pin "7") (pinfunction "7_7") (pintype "passive"))
      (node (ref "JP8") (pin "8") (pinfunction "8_8") (pintype "passive"))
      (node (ref "POT_A") (pin "P$3") (pinfunction "A_P$3") (pintype "passive"))
      (node (ref "POT_B") (pin "P$3") (pinfunction "A_P$3") (pintype "passive"))
      (node (ref "POT_C") (pin "P$3") (pinfunction "A_P$3") (pintype "passive"))
      (node (ref "Q2") (pin "2") (pinfunction "LID1_2") (pintype "power_in"))
      (node (ref "Q2") (pin "4") (pinfunction "LID2_4") (pintype "power_in"))
      (node (ref "Q5") (pin "E") (pinfunction "E_E") (pintype "passive"))
      (node (ref "Q6") (pin "E") (pinfunction "E_E") (pintype "passive"))
      (node (ref "Q7") (pin "E") (pinfunction "E_E") (pintype "passive"))
      (node (ref "R13") (pin "2") (pinfunction "2_2") (pintype "passive"))
      (node (ref "R17") (pin "2") (pinfunction "2_2") (pintype "passive"))
      (node (ref "R50") (pin "2") (pinfunction "2_2") (pintype "passive"))
      (node (ref "R69") (pin "1") (pinfunction "1_1") (pintype "passive"))
      (node (ref "R70") (pin "1") (pinfunction "1_1") (pintype "passive"))
      (node (ref "R71") (pin "1") (pinfunction "1_1") (pintype "passive"))
      (node (ref "R9") (pin "2") (pinfunction "2_2") (pintype "passive"))
      (node (ref "SLD_A") (pin "1") (pinfunction "A_1") (pintype "passive"))
      (node (ref "SLD_B") (pin "1") (pinfunction "A_1") (pintype "passive"))
      (node (ref "SLD_C") (pin "1") (pinfunction "A_1") (pintype "passive"))
      (node (ref "SW_A") (pin "1") (pinfunction "1_1") (pintype "passive"))
      (node (ref "SW_A") (pin "2") (pinfunction "2_2") (pintype "passive"))
      (node (ref "SW_B") (pin "1") (pinfunction "1_1") (pintype "passive"))
      (node (ref "SW_B") (pin "2") (pinfunction "2_2") (pintype "passive"))
      (node (ref "SW_C") (pin "1") (pinfunction "1_1") (pintype "passive"))
      (node (ref "SW_C") (pin "2") (pinfunction "2_2") (pintype "passive"))
      (node (ref "U$1") (pin "3") (pinfunction "GND_3") (pintype "power_in"))
      (node (ref "U1") (pin "16") (pinfunction "VSS_2_16") (pintype "power_in"))
      (node (ref "U1") (pin "31") (pinfunction "BOOT0_31") (pintype "input"))
      (node (ref "U1") (pin "32") (pinfunction "VSS_1_32") (pintype "power_in"))
      (node (ref "U2") (pin "11") (pinfunction "V-_11") (pintype "power_in"))
      (node (ref "U2") (pin "13") (pinfunction "-IN_13") (pintype "input"))
      (node (ref "U2") (pin "2") (pinfunction "-IN_2") (pintype "input"))
      (node (ref "U2") (pin "6") (pinfunction "-IN_6") (pintype "input"))
      (node (ref "U2") (pin "9") (pinfunction "-IN_9") (pintype "input"))
      (node (ref "U4") (pin "13") (pinfunction "-IN_13") (pintype "input"))
    )
    (net (code "24") (name "LEDS_SCK") (class "Default")
      (node (ref "IC1") (pin "3") (pinfunction "SCLK_3") (pintype "bidirectional"))
      (node (ref "U1") (pin "26") (pinfunction "PB3_26") (pintype "bidirectional"))
    )
    (net (code "25") (name "LEDS_SIN") (class "Default")
      (node (ref "IC1") (pin "2") (pinfunction "SIN_2") (pintype "bidirectional"))
      (node (ref "U1") (pin "28") (pinfunction "PB5_28") (pintype "bidirectional"))
    )
    (net (code "26") (name "Net-(C13-Pad1)") (class "Default")
      (node (ref "C13") (pin "1") (pinfunction "1_1") (pintype "passive"))
      (node (ref "L3") (pin "1") (pinfunction "1_1") (pintype "passive"))
    )
    (net (code "27") (name "Net-(C23-Pad1)") (class "Default")
      (node (ref "C23") (pin "1") (pinfunction "1_1") (pintype "passive"))
      (node (ref "C50") (pin "2") (pinfunction "2_2") (pintype "passive"))
    )
    (net (code "28") (name "Net-(C34-Pad2)") (class "Default")
      (node (ref "C34") (pin "2") (pinfunction "2_2") (pintype "passive"))
      (node (ref "Q2") (pin "1") (pinfunction "1_1") (pintype "passive"))
      (node (ref "R22") (pin "2") (pinfunction "2_2") (pintype "passive"))
    )
    (net (code "29") (name "Net-(D1-PadC)") (class "Default")
      (node (ref "D1") (pin "C") (pinfunction "C_C") (pintype "passive"))
      (node (ref "Q7") (pin "B") (pinfunction "B_B") (pintype "passive"))
      (node (ref "R66") (pin "2") (pinfunction "2_2") (pintype "passive"))
      (node (ref "R69") (pin "2") (pinfunction "2_2") (pintype "passive"))
    )
    (net (code "30") (name "Net-(D2-PadC)") (class "Default")
      (node (ref "D2") (pin "C") (pinfunction "C_C") (pintype "passive"))
      (node (ref "Q5") (pin "B") (pinfunction "B_B") (pintype "passive"))
      (node (ref "R67") (pin "2") (pinfunction "2_2") (pintype "passive"))
      (node (ref "R70") (pin "2") (pinfunction "2_2") (pintype "passive"))
    )
    (net (code "31") (name "Net-(D3-PadC)") (class "Default")
      (node (ref "D3") (pin "C") (pinfunction "C_C") (pintype "passive"))
      (node (ref "L4") (pin "2") (pinfunction "2_2") (pintype "passive"))
      (node (ref "L5") (pin "2") (pinfunction "2_2") (pintype "passive"))
    )
    (net (code "32") (name "Net-(D4-PadA)") (class "Default")
      (node (ref "D4") (pin "A") (pinfunction "A_A") (pintype "passive"))
      (node (ref "L1") (pin "2") (pinfunction "2_2") (pintype "passive"))
    )
    (net (code "33") (name "Net-(D5-PadC)") (class "Default")
      (node (ref "D5") (pin "C") (pinfunction "C_C") (pintype "passive"))
      (node (ref "Q6") (pin "B") (pinfunction "B_B") (pintype "passive"))
      (node (ref "R68") (pin "2") (pinfunction "2_2") (pintype "passive"))
      (node (ref "R71") (pin "2") (pinfunction "2_2") (pintype "passive"))
    )
    (net (code "34") (name "Net-(IC1-IREF)") (class "Default")
      (node (ref "IC1") (pin "23") (pinfunction "IREF_23") (pintype "bidirectional"))
      (node (ref "R50") (pin "1") (pinfunction "1_1") (pintype "passive"))
    )
    (net (code "35") (name "Net-(IC1-OUT1)") (class "Default")
      (node (ref "IC1") (pin "6") (pinfunction "OUT1_6") (pintype "bidirectional"))
      (node (ref "R31") (pin "2") (pinfunction "2_2") (pintype "passive"))
    )
    (net (code "36") (name "Net-(IC1-OUT2)") (class "Default")
      (node (ref "IC1") (pin "7") (pinfunction "OUT2_7") (pintype "bidirectional"))
      (node (ref "MODE_C") (pin "RED_C") (pinfunction "RED_RED_C") (pintype "bidirectional"))
    )
    (net (code "37") (name "Net-(IC1-OUT3)") (class "Default")
      (node (ref "IC1") (pin "8") (pinfunction "OUT3_8") (pintype "bidirectional"))
      (node (ref "MODE_C") (pin "GREEN_C") (pinfunction "GRN_GREEN_C") (pintype "bidirectional"))
    )
    (net (code "38") (name "Net-(IC1-OUT4)") (class "Default")
      (node (ref "IC1") (pin "9") (pinfunction "OUT4_9") (pintype "bidirectional"))
      (node (ref "MODE_A") (pin "GREEN_C") (pinfunction "GRN_GREEN_C") (pintype "bidirectional"))
    )
    (net (code "39") (name "Net-(IC1-OUT5)") (class "Default")
      (node (ref "IC1") (pin "10") (pinfunction "OUT5_10") (pintype "bidirectional"))
      (node (ref "MODE_A") (pin "RED_C") (pinfunction "RED_RED_C") (pintype "bidirectional"))
    )
    (net (code "40") (name "Net-(IC1-OUT6)") (class "Default")
      (node (ref "IC1") (pin "11") (pinfunction "OUT6_11") (pintype "bidirectional"))
      (node (ref "MODE_B") (pin "GREEN_C") (pinfunction "GRN_GREEN_C") (pintype "bidirectional"))
    )
    (net (code "41") (name "Net-(IC1-OUT7)") (class "Default")
      (node (ref "IC1") (pin "12") (pinfunction "OUT7_12") (pintype "bidirectional"))
      (node (ref "MODE_B") (pin "RED_C") (pinfunction "RED_RED_C") (pintype "bidirectional"))
    )
    (net (code "42") (name "Net-(IC1-OUT8)") (class "Default")
      (node (ref "IC1") (pin "13") (pinfunction "OUT8_13") (pintype "bidirectional"))
      (node (ref "LED10") (pin "GREEN_C") (pinfunction "GRN_GREEN_C") (pintype "bidirectional"))
    )
    (net (code "43") (name "Net-(IC1-OUT9)") (class "Default")
      (node (ref "IC1") (pin "14") (pinfunction "OUT9_14") (pintype "bidirectional"))
      (node (ref "LED10") (pin "RED_C") (pinfunction "RED_RED_C") (pintype "bidirectional"))
    )
    (net (code "44") (name "Net-(IC1-OUT10)") (class "Default")
      (node (ref "IC1") (pin "15") (pinfunction "OUT10_15") (pintype "bidirectional"))
      (node (ref "LED11") (pin "RED_C") (pinfunction "RED_RED_C") (pintype "bidirectional"))
    )
    (net (code "45") (name "Net-(IC1-OUT11)") (class "Default")
      (node (ref "IC1") (pin "16") (pinfunction "OUT11_16") (pintype "bidirectional"))
      (node (ref "LED11") (pin "GREEN_C") (pinfunction "GRN_GREEN_C") (pintype "bidirectional"))
    )
    (net (code "46") (name "Net-(IC1-OUT12)") (class "Default")
      (node (ref "IC1") (pin "17") (pinfunction "OUT12_17") (pintype "bidirectional"))
      (node (ref "LED12") (pin "RED_C") (pinfunction "RED_RED_C") (pintype "bidirectional"))
    )
    (net (code "47") (name "Net-(IC1-OUT13)") (class "Default")
      (node (ref "IC1") (pin "18") (pinfunction "OUT13_18") (pintype "bidirectional"))
      (node (ref "LED12") (pin "GREEN_C") (pinfunction "GRN_GREEN_C") (pintype "bidirectional"))
    )
    (net (code "48") (name "Net-(IC1-OUT14)") (class "Default")
      (node (ref "IC1") (pin "19") (pinfunction "OUT14_19") (pintype "bidirectional"))
      (node (ref "R19") (pin "2") (pinfunction "2_2") (pintype "passive"))
    )
    (net (code "49") (name "Net-(IC1-OUT15)") (class "Default")
      (node (ref "IC1") (pin "20") (pinfunction "OUT15_20") (pintype "bidirectional"))
      (node (ref "R30") (pin "2") (pinfunction "2_2") (pintype "passive"))
    )
    (net (code "50") (name "Net-(IC1-VCC)") (class "Default")
      (node (ref "C7") (pin "1") (pinfunction "1_1") (pintype "passive"))
      (node (ref "C8") (pin "1") (pinfunction "1_1") (pintype "passive"))
      (node (ref "IC1") (pin "24") (pinfunction "VCC_24") (pintype "bidirectional"))
      (node (ref "L2") (pin "1") (pinfunction "1_1") (pintype "passive"))
    )
    (net (code "51") (name "Net-(IC2-VI)") (class "Default")
      (node (ref "C15") (pin "1") (pinfunction "1_1") (pintype "passive"))
      (node (ref "IC2") (pin "1") (pinfunction "VI_1") (pintype "input"))
      (node (ref "L3") (pin "2") (pinfunction "2_2") (pintype "passive"))
    )
    (net (code "52") (name "Net-(IC3A-X0)") (class "Default")
      (node (ref "IC3") (pin "13") (pinfunction "X0_13") (pintype "bidirectional"))
      (node (ref "POT_C") (pin "P$2") (pinfunction "S_P$2") (pintype "passive"))
    )
    (net (code "53") (name "Net-(IC3A-X1)") (class "Default")
      (node (ref "IC3") (pin "14") (pinfunction "X1_14") (pintype "bidirectional"))
      (node (ref "SLD_C") (pin "2") (pinfunction "S_2") (pintype "passive"))
    )
    (net (code "54") (name "Net-(IC3A-X2)") (class "Default")
      (node (ref "IC3") (pin "15") (pinfunction "X2_15") (pintype "bidirectional"))
      (node (ref "SLD_B") (pin "2") (pinfunction "S_2") (pintype "passive"))
    )
    (net (code "55") (name "Net-(IC3A-X3)") (class "Default")
      (node (ref "IC3") (pin "12") (pinfunction "X3_12") (pintype "bidirectional"))
      (node (ref "POT_A") (pin "P$2") (pinfunction "S_P$2") (pintype "passive"))
    )
    (net (code "56") (name "Net-(IC3A-X4)") (class "Default")
      (node (ref "IC3") (pin "1") (pinfunction "X4_1") (pintype "bidirectional"))
      (node (ref "SLD_A") (pin "2") (pinfunction "S_2") (pintype "passive"))
    )
    (net (code "57") (name "Net-(IC3A-X6)") (class "Default")
      (node (ref "IC3") (pin "2") (pinfunction "X6_2") (pintype "bidirectional"))
      (node (ref "POT_B") (pin "P$2") (pinfunction "S_P$2") (pintype "passive"))
    )
    (net (code "58") (name "Net-(IC7-VI)") (class "Default")
      (node (ref "C20") (pin "1") (pinfunction "1_1") (pintype "passive"))
      (node (ref "IC7") (pin "3") (pinfunction "VI_3") (pintype "input"))
      (node (ref "L4") (pin "1") (pinfunction "1_1") (pintype "passive"))
    )
    (net (code "59") (name "Net-(IC9A-+IN)") (class "Default")
      (node (ref "IC9") (pin "3") (pinfunction "+IN_3") (pintype "input"))
      (node (ref "R8") (pin "2") (pinfunction "2_2") (pintype "passive"))
      (node (ref "R9") (pin "1") (pinfunction "1_1") (pintype "passive"))
    )
    (net (code "60") (name "Net-(IC9A--IN)") (class "Default")
      (node (ref "IC9") (pin "2") (pinfunction "-IN_2") (pintype "input"))
      (node (ref "R10") (pin "1") (pinfunction "1_1") (pintype "passive"))
    )
    (net (code "61") (name "Net-(IC9A-OUT)") (class "Default")
      (node (ref "IC9") (pin "1") (pinfunction "OUT_1") (pintype "output"))
      (node (ref "R7") (pin "2") (pinfunction "2_2") (pintype "passive"))
      (node (ref "R8") (pin "1") (pinfunction "1_1") (pintype "passive"))
    )
    (net (code "62") (name "Net-(IC9B-+IN)") (class "Default")
      (node (ref "IC9") (pin "5") (pinfunction "+IN_5") (pintype "input"))
      (node (ref "R12") (pin "2") (pinfunction "2_2") (pintype "passive"))
      (node (ref "R13") (pin "1") (pinfunction "1_1") (pintype "passive"))
    )
    (net (code "63") (name "Net-(IC9B--IN)") (class "Default")
      (node (ref "IC9") (pin "6") (pinfunction "-IN_6") (pintype "input"))
      (node (ref "R14") (pin "1") (pinfunction "1_1") (pintype "passive"))
    )
    (net (code "64") (name "Net-(IC9B-OUT)") (class "Default")
      (node (ref "IC9") (pin "7") (pinfunction "OUT_7") (pintype "output"))
      (node (ref "R11") (pin "2") (pinfunction "2_2") (pintype "passive"))
      (node (ref "R12") (pin "1") (pinfunction "1_1") (pintype "passive"))
    )
    (net (code "65") (name "Net-(IC9C-+IN)") (class "Default")
      (node (ref "IC9") (pin "10") (pinfunction "+IN_10") (pintype "input"))
      (node (ref "R16") (pin "2") (pinfunction "2_2") (pintype "passive"))
      (node (ref "R17") (pin "1") (pinfunction "1_1") (pintype "passive"))
    )
    (net (code "66") (name "Net-(IC9C--IN)") (class "Default")
      (node (ref "IC9") (pin "9") (pinfunction "-IN_9") (pintype "input"))
      (node (ref "R20") (pin "1") (pinfunction "1_1") (pintype "passive"))
    )
    (net (code "67") (name "Net-(IC9C-OUT)") (class "Default")
      (node (ref "IC9") (pin "8") (pinfunction "OUT_8") (pintype "output"))
      (node (ref "R15") (pin "2") (pinfunction "2_2") (pintype "passive"))
      (node (ref "R16") (pin "1") (pinfunction "1_1") (pintype "passive"))
    )
    (net (code "68") (name "Net-(IC9D--IN)") (class "Default")
      (node (ref "IC9") (pin "13") (pinfunction "-IN_13") (pintype "input"))
      (node (ref "IC9") (pin "14") (pinfunction "OUT_14") (pintype "output"))
    )
    (net (code "69") (name "Net-(J1-3)") (class "Default")
      (node (ref "C27") (pin "1") (pinfunction "1_1") (pintype "passive"))
      (node (ref "J1") (pin "P3") (pinfunction "3_P3") (pintype "passive"))
      (node (ref "R6") (pin "2") (pinfunction "2_2") (pintype "passive"))
    )
    (net (code "70") (name "Net-(J2-3)") (class "Default")
      (node (ref "C29") (pin "1") (pinfunction "1_1") (pintype "passive"))
      (node (ref "J2") (pin "P3") (pinfunction "3_P3") (pintype "passive"))
      (node (ref "R51") (pin "2") (pinfunction "2_2") (pintype "passive"))
    )
    (net (code "71") (name "Net-(J3-3)") (class "Default")
      (node (ref "J3") (pin "P3") (pinfunction "3_P3") (pintype "passive"))
      (node (ref "R68") (pin "1") (pinfunction "1_1") (pintype "passive"))
    )
    (net (code "72") (name "Net-(J4-3)") (class "Default")
      (node (ref "J4") (pin "P3") (pinfunction "3_P3") (pintype "passive"))
      (node (ref "R67") (pin "1") (pinfunction "1_1") (pintype "passive"))
    )
    (net (code "73") (name "Net-(J5-3)") (class "Default")
      (node (ref "C25") (pin "1") (pinfunction "1_1") (pintype "passive"))
      (node (ref "J5") (pin "P3") (pinfunction "3_P3") (pintype "passive"))
      (node (ref "R4") (pin "2") (pinfunction "2_2") (pintype "passive"))
    )
    (net (code "74") (name "Net-(J6-3)") (class "Default")
      (node (ref "J6") (pin "P3") (pinfunction "3_P3") (pintype "passive"))
      (node (ref "R66") (pin "1") (pinfunction "1_1") (pintype "passive"))
    )
    (net (code "75") (name "Net-(J7-3)") (class "Default")
      (node (ref "J7") (pin "P3") (pinfunction "3_P3") (pintype "passive"))
      (node (ref "R35") (pin "1") (pinfunction "1_1") (pintype "passive"))
      (node (ref "R41") (pin "1") (pinfunction "1_1") (pintype "passive"))
    )
    (net (code "76") (name "Net-(J8-3)") (class "Default")
      (node (ref "J8") (pin "P3") (pinfunction "3_P3") (pintype "passive"))
      (node (ref "R32") (pin "1") (pinfunction "1_1") (pintype "passive"))
      (node (ref "R33") (pin "1") (pinfunction "1_1") (pintype "passive"))
    )
    (net (code "77") (name "Net-(J9-3)") (class "Default")
      (node (ref "J9") (pin "P3") (pinfunction "3_P3") (pintype "passive"))
      (node (ref "R36") (pin "1") (pinfunction "1_1") (pintype "passive"))
      (node (ref "R37") (pin "1") (pinfunction "1_1") (pintype "passive"))
    )
    (net (code "78") (name "Net-(J10-3)") (class "Default")
      (node (ref "J10") (pin "P3") (pinfunction "3_P3") (pintype "passive"))
      (node (ref "R7") (pin "1") (pinfunction "1_1") (pintype "passive"))
    )
    (net (code "79") (name "Net-(J11-3)") (class "Default")
      (node (ref "J11") (pin "P3") (pinfunction "3_P3") (pintype "passive"))
      (node (ref "R11") (pin "1") (pinfunction "1_1") (pintype "passive"))
    )
    (net (code "80") (name "Net-(J12-3)") (class "Default")
      (node (ref "J12") (pin "P3") (pinfunction "3_P3") (pintype "passive"))
      (node (ref "R15") (pin "1") (pinfunction "1_1") (pintype "passive"))
    )
    (net (code "81") (name "Net-(Q2B-2)") (class "Default")
      (node (ref "C35") (pin "2") (pinfunction "2_2") (pintype "passive"))
      (node (ref "Q2") (pin "3") (pinfunction "2_3") (pintype "passive"))
      (node (ref "R21") (pin "2") (pinfunction "2_2") (pintype "passive"))
    )
    (net (code "82") (name "Net-(SLD_AA-C)") (class "Default")
      (node (ref "R19") (pin "1") (pinfunction "1_1") (pintype "passive"))
      (node (ref "SLD_A") (pin "E") (pinfunction "C_E") (pintype "passive"))
    )
    (net (code "83") (name "Net-(SLD_BA-C)") (class "Default")
      (node (ref "R30") (pin "1") (pinfunction "1_1") (pintype "passive"))
      (node (ref "SLD_B") (pin "E") (pinfunction "C_E") (pintype "passive"))
    )
    (net (code "84") (name "Net-(SLD_CA-C)") (class "Default")
      (node (ref "R31") (pin "1") (pinfunction "1_1") (pintype "passive"))
      (node (ref "SLD_C") (pin "E") (pinfunction "C_E") (pintype "passive"))
    )
    (net (code "85") (name "Net-(U1-PF0{slash}OSC_IN)") (class "Default")
      (node (ref "R21") (pin "1") (pinfunction "1_1") (pintype "passive"))
      (node (ref "U1") (pin "2") (pinfunction "PF0/OSC_IN_2") (pintype "bidirectional"))
    )
    (net (code "86") (name "Net-(U1-PF1{slash}OSC_OUT)") (class "Default")
      (node (ref "R22") (pin "1") (pinfunction "1_1") (pintype "passive"))
      (node (ref "U1") (pin "3") (pinfunction "PF1/OSC_OUT_3") (pintype "bidirectional"))
    )
    (net (code "87") (name "Net-(U2A-+IN)") (class "Default")
      (node (ref "C12") (pin "1") (pinfunction "1_1") (pintype "passive"))
      (node (ref "R29") (pin "1") (pinfunction "1_1") (pintype "passive"))
      (node (ref "R4") (pin "1") (pinfunction "1_1") (pintype "passive"))
      (node (ref "R5") (pin "2") (pinfunction "2_2") (pintype "passive"))
      (node (ref "U2") (pin "3") (pinfunction "+IN_3") (pintype "input"))
    )
    (net (code "88") (name "Net-(U2B-+IN)") (class "Default")
      (node (ref "C26") (pin "1") (pinfunction "1_1") (pintype "passive"))
      (node (ref "R26") (pin "2") (pinfunction "2_2") (pintype "passive"))
      (node (ref "R28") (pin "1") (pinfunction "1_1") (pintype "passive"))
      (node (ref "R6") (pin "1") (pinfunction "1_1") (pintype "passive"))
      (node (ref "U2") (pin "5") (pinfunction "+IN_5") (pintype "input"))
    )
    (net (code "89") (name "Net-(U2C-+IN)") (class "Default")
      (node (ref "C28") (pin "1") (pinfunction "1_1") (pintype "passive"))
      (node (ref "R51") (pin "1") (pinfunction "1_1") (pintype "passive"))
      (node (ref "R52") (pin "2") (pinfunction "2_2") (pintype "passive"))
      (node (ref "R53") (pin "1") (pinfunction "1_1") (pintype "passive"))
      (node (ref "U2") (pin "10") (pinfunction "+IN_10") (pintype "input"))
    )
    (net (code "90") (name "Net-(U2D-+IN)") (class "Default")
      (node (ref "U2") (pin "12") (pinfunction "+IN_12") (pintype "input"))
      (node (ref "U2") (pin "14") (pinfunction "OUT_14") (pintype "output"))
    )
    (net (code "91") (name "Net-(U4A-+IN)") (class "Default")
      (node (ref "C1") (pin "1") (pinfunction "1_1") (pintype "passive"))
      (node (ref "R41") (pin "2") (pinfunction "2_2") (pintype "passive"))
      (node (ref "R47") (pin "1") (pinfunction "1_1") (pintype "passive"))
      (node (ref "U4") (pin "3") (pinfunction "+IN_3") (pintype "input"))
    )
    (net (code "92") (name "Net-(U4A-OUT)") (class "Default")
      (node (ref "C1") (pin "2") (pinfunction "2_2") (pintype "passive"))
      (node (ref "R35") (pin "2") (pinfunction "2_2") (pintype "passive"))
      (node (ref "U4") (pin "1") (pinfunction "OUT_1") (pintype "output"))
    )
    (net (code "93") (name "Net-(U4B-+IN)") (class "Default")
      (node (ref "C2") (pin "1") (pinfunction "1_1") (pintype "passive"))
      (node (ref "R33") (pin "2") (pinfunction "2_2") (pintype "passive"))
      (node (ref "R34") (pin "1") (pinfunction "1_1") (pintype "passive"))
      (node (ref "U4") (pin "5") (pinfunction "+IN_5") (pintype "input"))
    )
    (net (code "94") (name "Net-(U4B-OUT)") (class "Default")
      (node (ref "C2") (pin "2") (pinfunction "2_2") (pintype "passive"))
      (node (ref "R32") (pin "2") (pinfunction "2_2") (pintype "passive"))
      (node (ref "U4") (pin "7") (pinfunction "OUT_7") (pintype "output"))
    )
    (net (code "95") (name "Net-(U4C-+IN)") (class "Default")
      (node (ref "C3") (pin "1") (pinfunction "1_1") (pintype "passive"))
      (node (ref "R37") (pin "2") (pinfunction "2_2") (pintype "passive"))
      (node (ref "R38") (pin "1") (pinfunction "1_1") (pintype "passive"))
      (node (ref "U4") (pin "10") (pinfunction "+IN_10") (pintype "input"))
    )
    (net (code "96") (name "Net-(U4C-OUT)") (class "Default")
      (node (ref "C3") (pin "2") (pinfunction "2_2") (pintype "passive"))
      (node (ref "R36") (pin "2") (pinfunction "2_2") (pintype "passive"))
      (node (ref "U4") (pin "8") (pinfunction "OUT_8") (pintype "output"))
    )
    (net (code "97") (name "Net-(U4D-+IN)") (class "Default")
      (node (ref "U4") (pin "12") (pinfunction "+IN_12") (pintype "input"))
      (node (ref "U4") (pin "14") (pinfunction "OUT_14") (pintype "output"))
    )
    (net (code "98") (name "POTS_ADDR_A") (class "Default")
      (node (ref "IC3") (pin "11") (pinfunction "A_11") (pintype "input"))
      (node (ref "U1") (pin "13") (pinfunction "PA7_13") (pintype "bidirectional"))
    )
    (net (code "99") (name "POTS_ADDR_B") (class "Default")
      (node (ref "IC3") (pin "10") (pinfunction "B_10") (pintype "input"))
      (node (ref "U1") (pin "18") (pinfunction "PA8_18") (pintype "bidirectional"))
    )
    (net (code "100") (name "POTS_ADDR_C") (class "Default")
      (node (ref "IC3") (pin "9") (pinfunction "C_9") (pintype "input"))
      (node (ref "U1") (pin "19") (pinfunction "PA9_19") (pintype "bidirectional"))
    )
    (net (code "101") (name "RESET") (class "Default")
      (node (ref "C36") (pin "1") (pinfunction "1_1") (pintype "passive"))
      (node (ref "JP6") (pin "4") (pinfunction "4_4") (pintype "passive"))
      (node (ref "R18") (pin "2") (pinfunction "2_2") (pintype "passive"))
      (node (ref "U1") (pin "4") (pinfunction "NRST_4") (pintype "bidirectional"))
    )
    (net (code "102") (name "SWCLK") (class "Default")
      (node (ref "JP6") (pin "3") (pinfunction "3_3") (pintype "passive"))
      (node (ref "U1") (pin "24") (pinfunction "PA14_24") (pintype "bidirectional"))
    )
    (net (code "103") (name "SWDIO") (class "Default")
      (node (ref "JP6") (pin "2") (pinfunction "2_2") (pintype "passive"))
      (node (ref "U1") (pin "23") (pinfunction "PA13_23") (pintype "bidirectional"))
    )
    (net (code "104") (name "SW_MODE_A") (class "Default")
      (node (ref "SW_A") (pin "3") (pinfunction "3_3") (pintype "passive"))
      (node (ref "SW_A") (pin "4") (pinfunction "4_4") (pintype "passive"))
      (node (ref "U1") (pin "27") (pinfunction "PB4_27") (pintype "bidirectional"))
    )
    (net (code "105") (name "SW_MODE_B") (class "Default")
      (node (ref "SW_B") (pin "3") (pinfunction "3_3") (pintype "passive"))
      (node (ref "SW_B") (pin "4") (pinfunction "4_4") (pintype "passive"))
      (node (ref "U1") (pin "29") (pinfunction "PB6_29") (pintype "bidirectional"))
    )
    (net (code "106") (name "SW_MODE_C") (class "Default")
      (node (ref "SW_C") (pin "3") (pinfunction "3_3") (pintype "passive"))
      (node (ref "SW_C") (pin "4") (pinfunction "4_4") (pintype "passive"))
      (node (ref "U1") (pin "30") (pinfunction "PB7_30") (pintype "bidirectional"))
    )
    (net (code "107") (name "VCC") (class "Default")
      (node (ref "C14") (pin "1") (pinfunction "1_1") (pintype "passive"))
      (node (ref "C21") (pin "1") (pinfunction "1_1") (pintype "passive"))
      (node (ref "C4") (pin "1") (pinfunction "1_1") (pintype "passive"))
      (node (ref "C50") (pin "1") (pinfunction "1_1") (pintype "passive"))
      (node (ref "IC4") (pin "4") (pinfunction "V+_4") (pintype "power_in"))
      (node (ref "L5") (pin "1") (pinfunction "1_1") (pintype "passive"))
      (node (ref "U4") (pin "4") (pinfunction "V+_4") (pintype "power_in"))
    )
    (net (code "108") (name "VEE") (class "Default")
      (node (ref "C16") (pin "2") (pinfunction "2_2") (pintype "passive"))
      (node (ref "C18") (pin "2") (pinfunction "2_2") (pintype "passive"))
      (node (ref "C23") (pin "2") (pinfunction "2_2") (pintype "passive"))
      (node (ref "L1") (pin "1") (pinfunction "1_1") (pintype "passive"))
      (node (ref "R1") (pin "1") (pinfunction "1_1") (pintype "passive"))
      (node (ref "U4") (pin "11") (pinfunction "V-_11") (pintype "power_in"))
    )
    (net (code "109") (name "VREF_BIAS") (class "Default")
      (node (ref "C22") (pin "+") (pinfunction "+_+") (pintype "passive"))
      (node (ref "U$1") (pin "2") (pinfunction "VOUT_2") (pintype "output"))
      (node (ref "U4") (pin "2") (pinfunction "-IN_2") (pintype "input"))
      (node (ref "U4") (pin "6") (pinfunction "-IN_6") (pintype "input"))
      (node (ref "U4") (pin "9") (pinfunction "-IN_9") (pintype "input"))
    )
    (net (code "110") (name "unconnected-(IC1-LAT-Pad4)") (class "Default")
      (node (ref "IC1") (pin "4") (pinfunction "LAT_4") (pintype "bidirectional"))
    )
    (net (code "111") (name "unconnected-(IC1-OUT0-Pad5)") (class "Default")
      (node (ref "IC1") (pin "5") (pinfunction "OUT0_5") (pintype "bidirectional"))
    )
    (net (code "112") (name "unconnected-(IC1-SOUT-Pad22)") (class "Default")
      (node (ref "IC1") (pin "22") (pinfunction "SOUT_22") (pintype "bidirectional"))
    )
    (net (code "113") (name "unconnected-(IC3A-X5-Pad5)") (class "Default")
      (node (ref "IC3") (pin "5") (pinfunction "X5_5") (pintype "bidirectional"))
    )
    (net (code "114") (name "unconnected-(IC3A-X7-Pad4)") (class "Default")
      (node (ref "IC3") (pin "4") (pinfunction "X7_4") (pintype "bidirectional"))
    )
    (net (code "115") (name "unconnected-(J7-2-PadP2)") (class "Default")
      (node (ref "J7") (pin "P2") (pinfunction "2_P2") (pintype "passive"))
    )
    (net (code "116") (name "unconnected-(J8-2-PadP2)") (class "Default")
      (node (ref "J8") (pin "P2") (pinfunction "2_P2") (pintype "passive"))
    )
    (net (code "117") (name "unconnected-(J9-2-PadP2)") (class "Default")
      (node (ref "J9") (pin "P2") (pinfunction "2_P2") (pintype "passive"))
    )
    (net (code "118") (name "unconnected-(J10-2-PadP2)") (class "Default")
      (node (ref "J10") (pin "P2") (pinfunction "2_P2") (pintype "passive"))
    )
    (net (code "119") (name "unconnected-(J11-2-PadP2)") (class "Default")
      (node (ref "J11") (pin "P2") (pinfunction "2_P2") (pintype "passive"))
    )
    (net (code "120") (name "unconnected-(J12-2-PadP2)") (class "Default")
      (node (ref "J12") (pin "P2") (pinfunction "2_P2") (pintype "passive"))
    )
    (net (code "121") (name "unconnected-(JP8-Pad1)") (class "Default")
      (node (ref "JP8") (pin "1") (pinfunction "1_1") (pintype "passive"))
    )
    (net (code "122") (name "unconnected-(JP8-Pad9)") (class "Default")
      (node (ref "JP8") (pin "9") (pinfunction "9_9") (pintype "passive"))
    )
    (net (code "123") (name "unconnected-(R42-A-PadP$3)") (class "Default")
      (node (ref "R42") (pin "P$3") (pinfunction "A_P$3") (pintype "passive"))
    )
    (net (code "124") (name "unconnected-(R42-E-PadP$1)") (class "Default")
      (node (ref "R42") (pin "P$1") (pinfunction "E_P$1") (pintype "passive"))
    )
    (net (code "125") (name "unconnected-(R42-S-PadP$2)") (class "Default")
      (node (ref "R42") (pin "P$2") (pinfunction "S_P$2") (pintype "passive"))
    )
  )
)
